# MAIN-BOARD.net
KiCad netlist of a schematic drawn in Altium Designer
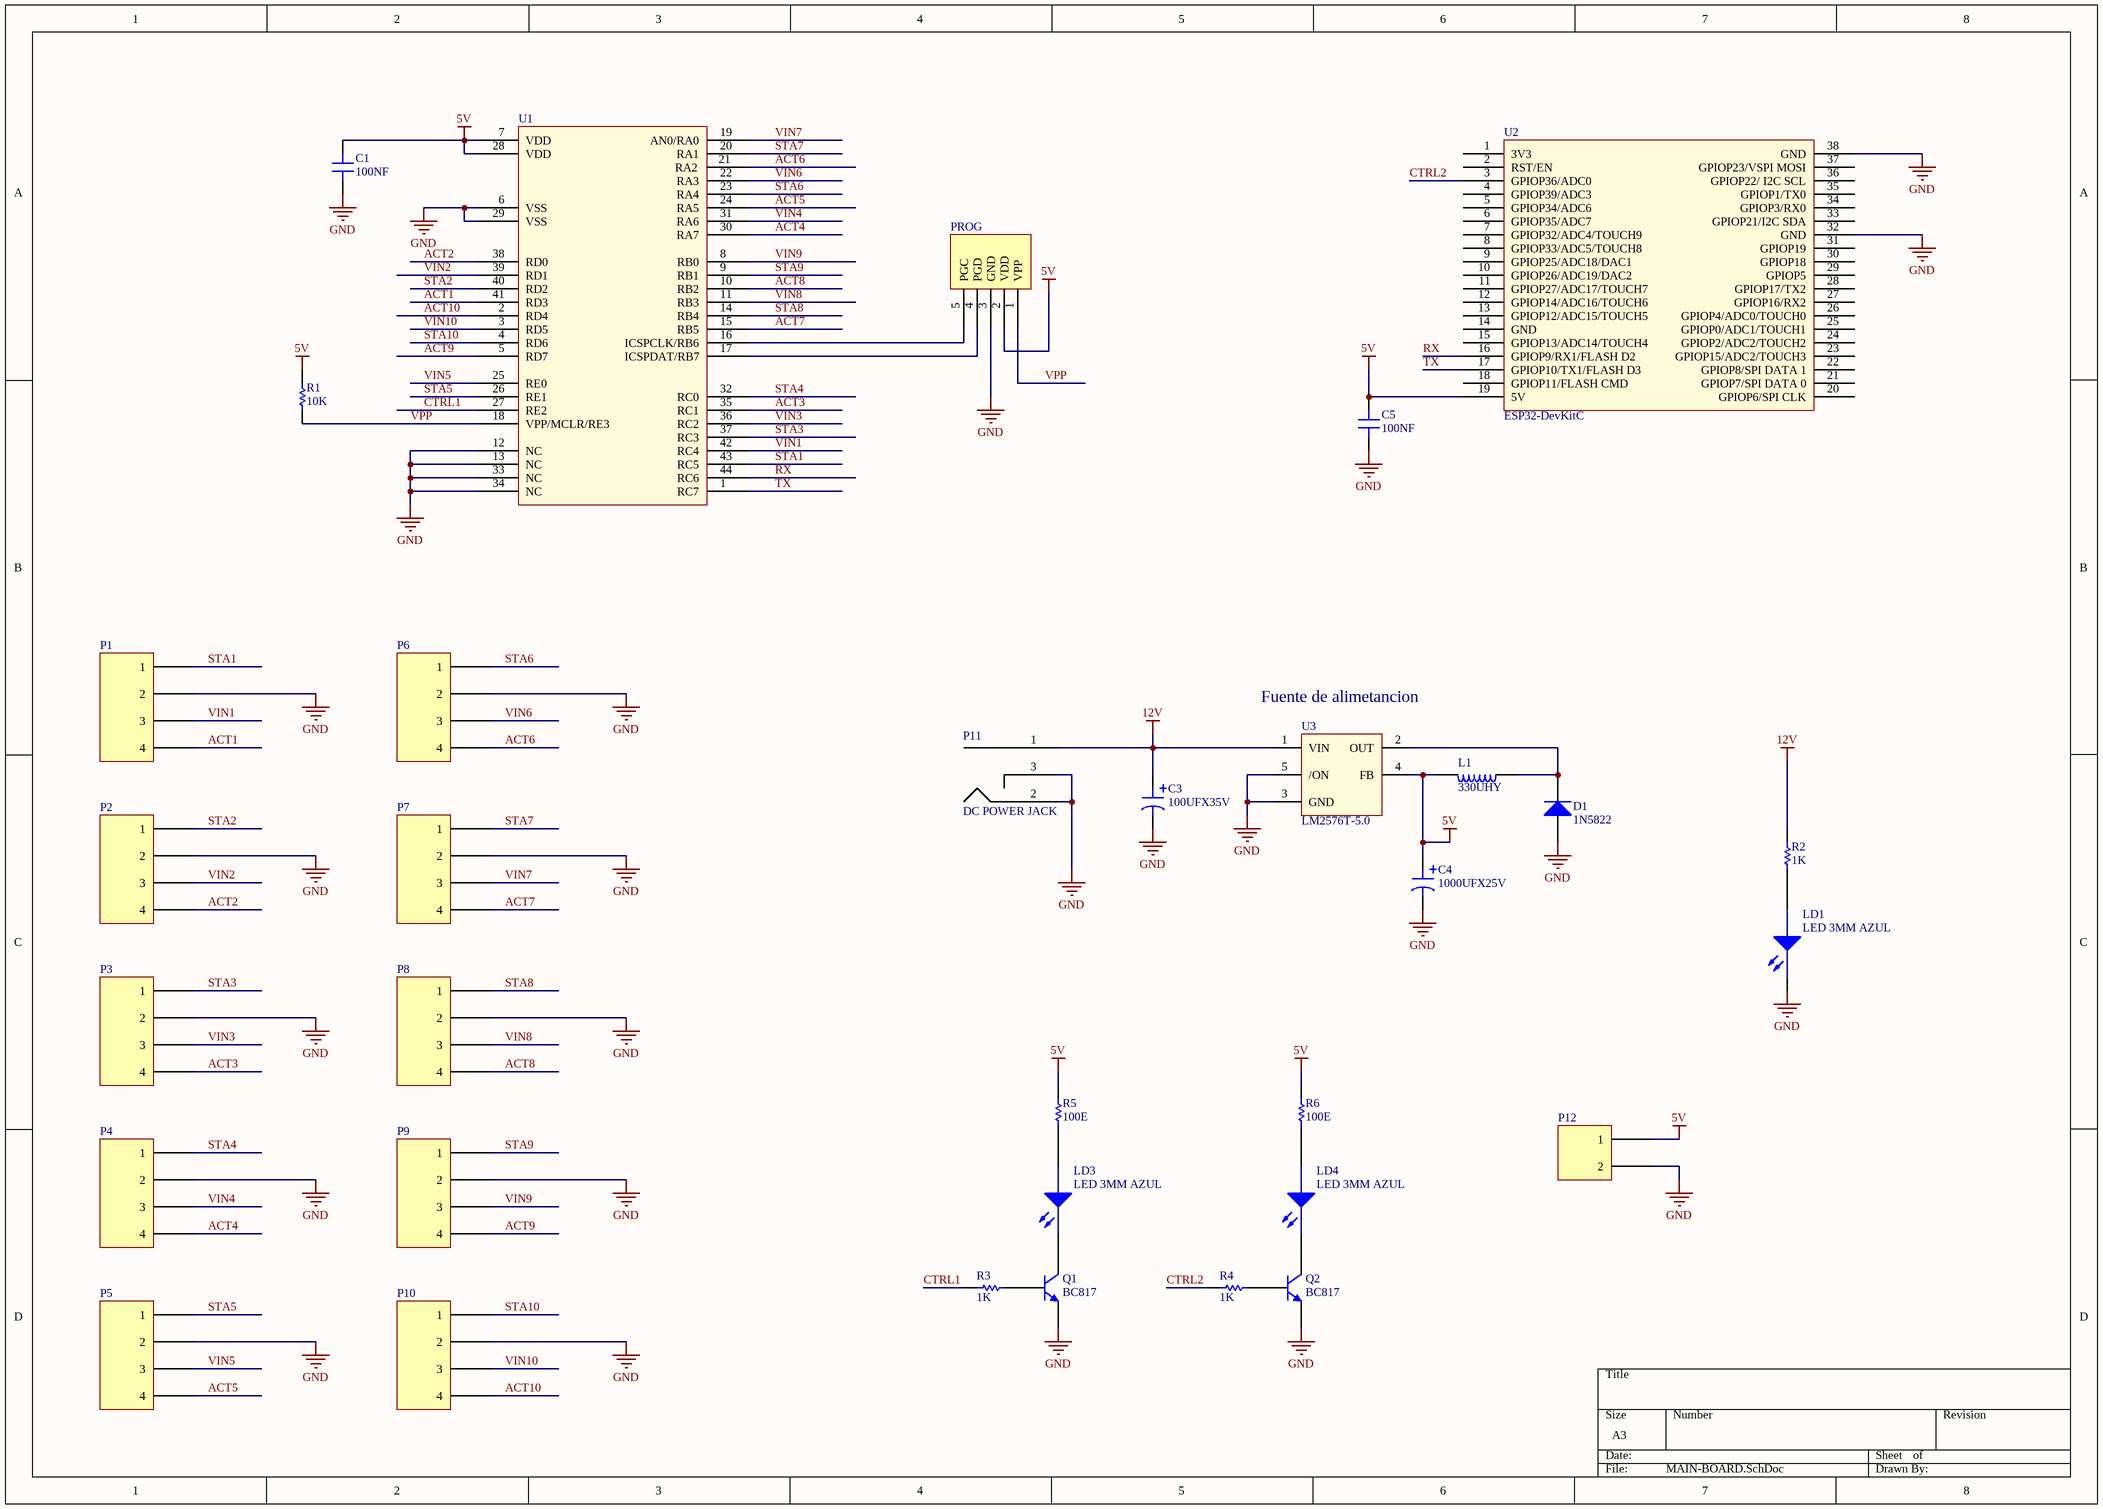
[diagram p0: MAIN-BOARD.SchDoc]

(export (version "E")
  (design (tool "Eeschema 10.0.6"))
  (components
    (comp (ref "C1")
      (value "100NF")
      (footprint "CAP.SMD.0805")
      (description "100NFX50V X7R 10% CER.MULT. SMD 0805")
      (libsource (lib "Libreria-Capacitores") (part "Capacitor 100NFX50V X7R 10% CER.MULT. SMD 0805"))
    )
    (comp (ref "C3")
      (value "100UFX35V")
      (footprint "CAP-ELEC-8X11")
      (description "100UFX35V 85°C 8x11 ELE.RAD AISHI")
      (libsource (lib "Libreria-Capacitores") (part "Capacitor Electrolitico 100UFX35V 85°C 8x11 ELE.RAD AISHI"))
    )
    (comp (ref "C4")
      (value "1000UFX25V")
      (footprint "CAP-ELEC-12.5X20")
      (description "1000UFX25V 85°C 12.5X20 ELE.RAD AISHI")
      (libsource (lib "Libreria-Capacitores") (part "Capacitor Electrolitico 1000UFX25V 85°C 12.5X20 ELE.RAD AISHI"))
    )
    (comp (ref "C5")
      (value "100NF")
      (footprint "CAP.SMD.0805")
      (description "100NFX50V X7R 10% CER.MULT. SMD 0805")
      (libsource (lib "Libreria-Capacitores") (part "Capacitor 100NFX50V X7R 10% CER.MULT. SMD 0805"))
    )
    (comp (ref "D1")
      (value "1N5822")
      (footprint "Diode 1N5822")
      (description "Diodo Schottky 1N5822 3A 40V")
      (libsource (lib "Libreria-Diodos") (part "Diodo Schottky 1N5822 3A 40V"))
    )
    (comp (ref "L1")
      (value "330UHY")
      (footprint "Inductor Radial DR1213")
      (description "330UHY 0.3R 1.4A RAD. 15.5X15.5MM")
      (libsource (lib "Libreria-Inductores") (part "Inductor Radial 330UHY 0.3R 1.4A RAD. 15.5X15.5MM"))
    )
    (comp (ref "LD1")
      (value "LED 3MM AZUL")
      (footprint "LED 3MM AZUL")
      (description "LED 3MM AZUL WC SUPER BRILLO 1250mcd 30潞 204-10SUBC/C470/S400-A6 PATAS 14MM")
      (libsource (lib "Libreria-LEDs") (part "LED 3MM AZUL WC SUPER BRILLO 1250mcd 30潞 204-10SUBC/C470/S400-A6 PATAS 14MM"))
    )
    (comp (ref "LD3")
      (value "LED 3MM AZUL")
      (footprint "LED 3MM AZUL")
      (description "LED 3MM AZUL WC SUPER BRILLO 1250mcd 30潞 204-10SUBC/C470/S400-A6 PATAS 14MM")
      (libsource (lib "Libreria-LEDs") (part "LED 3MM AZUL WC SUPER BRILLO 1250mcd 30潞 204-10SUBC/C470/S400-A6 PATAS 14MM"))
    )
    (comp (ref "LD4")
      (value "LED 3MM AZUL")
      (footprint "LED 3MM AZUL")
      (description "LED 3MM AZUL WC SUPER BRILLO 1250mcd 30潞 204-10SUBC/C470/S400-A6 PATAS 14MM")
      (libsource (lib "Libreria-LEDs") (part "LED 3MM AZUL WC SUPER BRILLO 1250mcd 30潞 204-10SUBC/C470/S400-A6 PATAS 14MM"))
    )
    (comp (ref "P1")
      (value "CONECTOR PWXXS MA-04 VERTICAL P=3.96MM PW0")
      (footprint "CONECTOR PWXXS MA-04 VERTICAL P=3.96MM")
      (libsource (lib "Libreria-Conectores") (part "CONECTOR PWXXS MA-04 VERTICAL P=3.96MM PW04S"))
    )
    (comp (ref "P2")
      (value "CONECTOR PWXXS MA-04 VERTICAL P=3.96MM PW0")
      (footprint "CONECTOR PWXXS MA-04 VERTICAL P=3.96MM")
      (libsource (lib "Libreria-Conectores") (part "CONECTOR PWXXS MA-04 VERTICAL P=3.96MM PW04S"))
    )
    (comp (ref "P3")
      (value "CONECTOR PWXXS MA-04 VERTICAL P=3.96MM PW0")
      (footprint "CONECTOR PWXXS MA-04 VERTICAL P=3.96MM")
      (libsource (lib "Libreria-Conectores") (part "CONECTOR PWXXS MA-04 VERTICAL P=3.96MM PW04S"))
    )
    (comp (ref "P4")
      (value "CONECTOR PWXXS MA-04 VERTICAL P=3.96MM PW0")
      (footprint "CONECTOR PWXXS MA-04 VERTICAL P=3.96MM")
      (libsource (lib "Libreria-Conectores") (part "CONECTOR PWXXS MA-04 VERTICAL P=3.96MM PW04S"))
    )
    (comp (ref "P5")
      (value "CONECTOR PWXXS MA-04 VERTICAL P=3.96MM PW0")
      (footprint "CONECTOR PWXXS MA-04 VERTICAL P=3.96MM")
      (libsource (lib "Libreria-Conectores") (part "CONECTOR PWXXS MA-04 VERTICAL P=3.96MM PW04S"))
    )
    (comp (ref "P6")
      (value "CONECTOR PWXXS MA-04 VERTICAL P=3.96MM PW0")
      (footprint "CONECTOR PWXXS MA-04 VERTICAL P=3.96MM")
      (libsource (lib "Libreria-Conectores") (part "CONECTOR PWXXS MA-04 VERTICAL P=3.96MM PW04S"))
    )
    (comp (ref "P7")
      (value "CONECTOR PWXXS MA-04 VERTICAL P=3.96MM PW0")
      (footprint "CONECTOR PWXXS MA-04 VERTICAL P=3.96MM")
      (libsource (lib "Libreria-Conectores") (part "CONECTOR PWXXS MA-04 VERTICAL P=3.96MM PW04S"))
    )
    (comp (ref "P8")
      (value "CONECTOR PWXXS MA-04 VERTICAL P=3.96MM PW0")
      (footprint "CONECTOR PWXXS MA-04 VERTICAL P=3.96MM")
      (libsource (lib "Libreria-Conectores") (part "CONECTOR PWXXS MA-04 VERTICAL P=3.96MM PW04S"))
    )
    (comp (ref "P9")
      (value "CONECTOR PWXXS MA-04 VERTICAL P=3.96MM PW0")
      (footprint "CONECTOR PWXXS MA-04 VERTICAL P=3.96MM")
      (libsource (lib "Libreria-Conectores") (part "CONECTOR PWXXS MA-04 VERTICAL P=3.96MM PW04S"))
    )
    (comp (ref "P10")
      (value "CONECTOR PWXXS MA-04 VERTICAL P=3.96MM PW0")
      (footprint "CONECTOR PWXXS MA-04 VERTICAL P=3.96MM")
      (libsource (lib "Libreria-Conectores") (part "CONECTOR PWXXS MA-04 VERTICAL P=3.96MM PW04S"))
    )
    (comp (ref "P11")
      (value "DC POWER JACK")
      (footprint "VAR-DC-JACK")
      (description "DC POWER JACK 90 GRA. 2MM")
      (libsource (lib "Libreria-Varios") (part "DC POWER JACK 90 GRA. 2MM"))
    )
    (comp (ref "P12")
      (value "BORNE 2P P=5MM 1.5MM2 15A AZUL XY301V-2P")
      (footprint "CON-BOR-X2-5MM")
      (libsource (lib "Libreria-Conectores") (part "BORNE 2P P=5MM 1.5MM2 15A AZUL XY301V-2P"))
    )
    (comp (ref "PROG")
      (value "In-Serial Circuit Programmer Header")
      (footprint "PIC ICSP")
      (libsource (lib "Libreria-Conectores") (part "In-Serial Circuit Programmer Header"))
    )
    (comp (ref "Q1")
      (value "BC817")
      (footprint "NPN.SMD.SOT23")
      (description "BC817-40 TRA.NPN 45V0.5A 0.25W SOT23")
      (libsource (lib "Libreria-Transistores") (part "Transistor BC817-40 TRA.NPN 45V0.5A 0.25W SOT23"))
    )
    (comp (ref "Q2")
      (value "BC817")
      (footprint "NPN.SMD.SOT23")
      (description "BC817-40 TRA.NPN 45V0.5A 0.25W SOT23")
      (libsource (lib "Libreria-Transistores") (part "Transistor BC817-40 TRA.NPN 45V0.5A 0.25W SOT23"))
    )
    (comp (ref "R1")
      (value "10K")
      (footprint "RES.SMD.103")
      (description "10K 5% 0805 1/8W RES.SMD")
      (libsource (lib "Libreria-Resistencias") (part "Resistencia 10K 5% 0805 1/8W"))
    )
    (comp (ref "R2")
      (value "1K")
      (footprint "RES.SMD.102")
      (description "1K 5% 0805 1/8W RES.SMD")
      (libsource (lib "Libreria-Resistencias") (part "Resistencia 1K 5% 0805 1/8W"))
    )
    (comp (ref "R3")
      (value "1K")
      (footprint "RES.SMD.102")
      (description "1K 5% 0805 1/8W RES.SMD")
      (libsource (lib "Libreria-Resistencias") (part "Resistencia 1K 5% 0805 1/8W"))
    )
    (comp (ref "R4")
      (value "1K")
      (footprint "RES.SMD.102")
      (description "1K 5% 0805 1/8W RES.SMD")
      (libsource (lib "Libreria-Resistencias") (part "Resistencia 1K 5% 0805 1/8W"))
    )
    (comp (ref "R5")
      (value "100E")
      (footprint "RES.SMD.101")
      (description "100E 5% 0805 1/8W RES.SMD")
      (libsource (lib "Libreria-Resistencias") (part "Resistencia 100E 5% 0805 1/8W"))
    )
    (comp (ref "R6")
      (value "100E")
      (footprint "RES.SMD.101")
      (description "100E 5% 0805 1/8W RES.SMD")
      (libsource (lib "Libreria-Resistencias") (part "Resistencia 100E 5% 0805 1/8W"))
    )
    (comp (ref "U1")
      (value "PIC16F18875-I/PT 44 TQFP 14KB Flash, 1KB RAM, 256B EE, 10b ADC2")
      (footprint "44TQFP - PIC16F18875")
      (libsource (lib "Libreria-Semiconductores") (part "PIC16F18875-I/PT 44 TQFP 14KB Flash, 1KB RAM, 256B EE, 10b ADC2"))
    )
    (comp (ref "U2")
      (value "ESP32-DevKitC")
      (footprint "ESP32-DevKitC")
      (libsource (lib "Libreria-Arduino") (part "ESP32-DevKitC"))
    )
    (comp (ref "U3")
      (value "LM2576T-5.0")
      (footprint "LM2576T-5.0")
      (description "LM2576T-5.0 TO220 3A.STEP.DOWN.VOLT.REG.")
      (libsource (lib "Libreria-Semiconductores") (part "LM2576T-5.0 TO220 3A.STEP.DOWN.VOLT.REG."))
    )
  )
  (nets
    (net (code "1") (name "/ACT1") (class "Default")
      (node (ref "P1") (pin "4") (pinfunction "4_4") (pintype "passive"))
      (node (ref "U1") (pin "41") (pinfunction "RD3_41") (pintype "passive"))
    )
    (net (code "2") (name "/ACT2") (class "Default")
      (node (ref "P2") (pin "4") (pinfunction "4_4") (pintype "passive"))
      (node (ref "U1") (pin "38") (pinfunction "RD0_38") (pintype "passive"))
    )
    (net (code "3") (name "/ACT3") (class "Default")
      (node (ref "P3") (pin "4") (pinfunction "4_4") (pintype "passive"))
      (node (ref "U1") (pin "35") (pinfunction "RC1_35") (pintype "passive"))
    )
    (net (code "4") (name "/ACT4") (class "Default")
      (node (ref "P4") (pin "4") (pinfunction "4_4") (pintype "passive"))
      (node (ref "U1") (pin "30") (pinfunction "RA7_30") (pintype "passive"))
    )
    (net (code "5") (name "/ACT5") (class "Default")
      (node (ref "P5") (pin "4") (pinfunction "4_4") (pintype "passive"))
      (node (ref "U1") (pin "24") (pinfunction "RA5_24") (pintype "passive"))
    )
    (net (code "6") (name "/ACT6") (class "Default")
      (node (ref "P6") (pin "4") (pinfunction "4_4") (pintype "passive"))
      (node (ref "U1") (pin "21") (pinfunction "RA2_21") (pintype "passive"))
    )
    (net (code "7") (name "/ACT7") (class "Default")
      (node (ref "P7") (pin "4") (pinfunction "4_4") (pintype "passive"))
      (node (ref "U1") (pin "15") (pinfunction "RB5_15") (pintype "passive"))
    )
    (net (code "8") (name "/ACT8") (class "Default")
      (node (ref "P8") (pin "4") (pinfunction "4_4") (pintype "passive"))
      (node (ref "U1") (pin "10") (pinfunction "RB2_10") (pintype "passive"))
    )
    (net (code "9") (name "/ACT9") (class "Default")
      (node (ref "P9") (pin "4") (pinfunction "4_4") (pintype "passive"))
      (node (ref "U1") (pin "5") (pinfunction "RD7_5") (pintype "passive"))
    )
    (net (code "10") (name "/ACT10") (class "Default")
      (node (ref "P10") (pin "4") (pinfunction "4_4") (pintype "passive"))
      (node (ref "U1") (pin "2") (pinfunction "RD4_2") (pintype "passive"))
    )
    (net (code "11") (name "/CTRL1") (class "Default")
      (node (ref "R3") (pin "2") (pinfunction "2_2") (pintype "passive"))
      (node (ref "U1") (pin "27") (pinfunction "RE2_27") (pintype "passive"))
    )
    (net (code "12") (name "/CTRL2") (class "Default")
      (node (ref "R4") (pin "2") (pinfunction "2_2") (pintype "passive"))
      (node (ref "U2") (pin "3") (pinfunction "GPIOP36/ADC0_3") (pintype "passive"))
    )
    (net (code "13") (name "/RX") (class "Default")
      (node (ref "U1") (pin "44") (pinfunction "RC6_44") (pintype "passive"))
      (node (ref "U2") (pin "16") (pinfunction "GPIOP9/RX1/FLASH_D2_16") (pintype "passive"))
    )
    (net (code "14") (name "/STA1") (class "Default")
      (node (ref "P1") (pin "1") (pinfunction "1_1") (pintype "passive"))
      (node (ref "U1") (pin "43") (pinfunction "RC5_43") (pintype "passive"))
    )
    (net (code "15") (name "/STA2") (class "Default")
      (node (ref "P2") (pin "1") (pinfunction "1_1") (pintype "passive"))
      (node (ref "U1") (pin "40") (pinfunction "RD2_40") (pintype "passive"))
    )
    (net (code "16") (name "/STA3") (class "Default")
      (node (ref "P3") (pin "1") (pinfunction "1_1") (pintype "passive"))
      (node (ref "U1") (pin "37") (pinfunction "RC3_37") (pintype "passive"))
    )
    (net (code "17") (name "/STA4") (class "Default")
      (node (ref "P4") (pin "1") (pinfunction "1_1") (pintype "passive"))
      (node (ref "U1") (pin "32") (pinfunction "RC0_32") (pintype "passive"))
    )
    (net (code "18") (name "/STA5") (class "Default")
      (node (ref "P5") (pin "1") (pinfunction "1_1") (pintype "passive"))
      (node (ref "U1") (pin "26") (pinfunction "RE1_26") (pintype "passive"))
    )
    (net (code "19") (name "/STA6") (class "Default")
      (node (ref "P6") (pin "1") (pinfunction "1_1") (pintype "passive"))
      (node (ref "U1") (pin "23") (pinfunction "RA4_23") (pintype "passive"))
    )
    (net (code "20") (name "/STA7") (class "Default")
      (node (ref "P7") (pin "1") (pinfunction "1_1") (pintype "passive"))
      (node (ref "U1") (pin "20") (pinfunction "RA1_20") (pintype "passive"))
    )
    (net (code "21") (name "/STA8") (class "Default")
      (node (ref "P8") (pin "1") (pinfunction "1_1") (pintype "passive"))
      (node (ref "U1") (pin "14") (pinfunction "RB4_14") (pintype "passive"))
    )
    (net (code "22") (name "/STA9") (class "Default")
      (node (ref "P9") (pin "1") (pinfunction "1_1") (pintype "passive"))
      (node (ref "U1") (pin "9") (pinfunction "RB1_9") (pintype "passive"))
    )
    (net (code "23") (name "/STA10") (class "Default")
      (node (ref "P10") (pin "1") (pinfunction "1_1") (pintype "passive"))
      (node (ref "U1") (pin "4") (pinfunction "RD6_4") (pintype "passive"))
    )
    (net (code "24") (name "/TX") (class "Default")
      (node (ref "U1") (pin "1") (pinfunction "RC7_1") (pintype "passive"))
      (node (ref "U2") (pin "17") (pinfunction "GPIOP10/TX1/FLASH_D3_17") (pintype "passive"))
    )
    (net (code "25") (name "/VIN1") (class "Default")
      (node (ref "P1") (pin "3") (pinfunction "3_3") (pintype "passive"))
      (node (ref "U1") (pin "42") (pinfunction "RC4_42") (pintype "passive"))
    )
    (net (code "26") (name "/VIN2") (class "Default")
      (node (ref "P2") (pin "3") (pinfunction "3_3") (pintype "passive"))
      (node (ref "U1") (pin "39") (pinfunction "RD1_39") (pintype "passive"))
    )
    (net (code "27") (name "/VIN3") (class "Default")
      (node (ref "P3") (pin "3") (pinfunction "3_3") (pintype "passive"))
      (node (ref "U1") (pin "36") (pinfunction "RC2_36") (pintype "passive"))
    )
    (net (code "28") (name "/VIN4") (class "Default")
      (node (ref "P4") (pin "3") (pinfunction "3_3") (pintype "passive"))
      (node (ref "U1") (pin "31") (pinfunction "RA6_31") (pintype "passive"))
    )
    (net (code "29") (name "/VIN5") (class "Default")
      (node (ref "P5") (pin "3") (pinfunction "3_3") (pintype "passive"))
      (node (ref "U1") (pin "25") (pinfunction "RE0_25") (pintype "passive"))
    )
    (net (code "30") (name "/VIN6") (class "Default")
      (node (ref "P6") (pin "3") (pinfunction "3_3") (pintype "passive"))
      (node (ref "U1") (pin "22") (pinfunction "RA3_22") (pintype "passive"))
    )
    (net (code "31") (name "/VIN7") (class "Default")
      (node (ref "P7") (pin "3") (pinfunction "3_3") (pintype "passive"))
      (node (ref "U1") (pin "19") (pinfunction "AN0/RA0_19") (pintype "passive"))
    )
    (net (code "32") (name "/VIN8") (class "Default")
      (node (ref "P8") (pin "3") (pinfunction "3_3") (pintype "passive"))
      (node (ref "U1") (pin "11") (pinfunction "RB3_11") (pintype "passive"))
    )
    (net (code "33") (name "/VIN9") (class "Default")
      (node (ref "P9") (pin "3") (pinfunction "3_3") (pintype "passive"))
      (node (ref "U1") (pin "8") (pinfunction "RB0_8") (pintype "passive"))
    )
    (net (code "34") (name "/VIN10") (class "Default")
      (node (ref "P10") (pin "3") (pinfunction "3_3") (pintype "passive"))
      (node (ref "U1") (pin "3") (pinfunction "RD5_3") (pintype "passive"))
    )
    (net (code "35") (name "/VPP") (class "Default")
      (node (ref "PROG") (pin "1") (pinfunction "VPP_1") (pintype "passive"))
      (node (ref "R1") (pin "1") (pinfunction "1_1") (pintype "passive"))
      (node (ref "U1") (pin "18") (pinfunction "VPP/MCLR/RE3_18") (pintype "passive"))
    )
    (net (code "36") (name "5V") (class "Default")
      (node (ref "C1") (pin "2") (pinfunction "2_2") (pintype "passive"))
      (node (ref "C4") (pin "1") (pinfunction "1_1") (pintype "passive"))
      (node (ref "C5") (pin "2") (pinfunction "2_2") (pintype "passive"))
      (node (ref "L1") (pin "1") (pinfunction "1_1") (pintype "passive"))
      (node (ref "P12") (pin "1") (pinfunction "1_1") (pintype "passive"))
      (node (ref "PROG") (pin "2") (pinfunction "VDD_2") (pintype "passive"))
      (node (ref "R1") (pin "2") (pinfunction "2_2") (pintype "passive"))
      (node (ref "R5") (pin "2") (pinfunction "2_2") (pintype "passive"))
      (node (ref "R6") (pin "2") (pinfunction "2_2") (pintype "passive"))
      (node (ref "U1") (pin "28") (pinfunction "VDD_28") (pintype "passive"))
      (node (ref "U1") (pin "7") (pinfunction "VDD_7") (pintype "passive"))
      (node (ref "U2") (pin "19") (pinfunction "5V_19") (pintype "passive"))
      (node (ref "U3") (pin "4") (pinfunction "FB_4") (pintype "passive"))
    )
    (net (code "37") (name "12V") (class "Default")
      (node (ref "C3") (pin "1") (pinfunction "1_1") (pintype "passive"))
      (node (ref "P11") (pin "1") (pinfunction "1_1") (pintype "passive"))
      (node (ref "R2") (pin "2") (pinfunction "2_2") (pintype "passive"))
      (node (ref "U3") (pin "1") (pinfunction "VIN_1") (pintype "passive"))
    )
    (net (code "38") (name "GND") (class "Default")
      (node (ref "C1") (pin "1") (pinfunction "1_1") (pintype "passive"))
      (node (ref "C3") (pin "2") (pinfunction "2_2") (pintype "passive"))
      (node (ref "C4") (pin "2") (pinfunction "2_2") (pintype "passive"))
      (node (ref "C5") (pin "1") (pinfunction "1_1") (pintype "passive"))
      (node (ref "D1") (pin "A") (pinfunction "A_A") (pintype "passive"))
      (node (ref "LD1") (pin "K") (pinfunction "KB_K") (pintype "passive"))
      (node (ref "P1") (pin "2") (pinfunction "2_2") (pintype "passive"))
      (node (ref "P10") (pin "2") (pinfunction "2_2") (pintype "passive"))
      (node (ref "P11") (pin "2") (pinfunction "2_2") (pintype "passive"))
      (node (ref "P11") (pin "3") (pinfunction "3_3") (pintype "passive"))
      (node (ref "P12") (pin "2") (pinfunction "2_2") (pintype "passive"))
      (node (ref "P2") (pin "2") (pinfunction "2_2") (pintype "passive"))
      (node (ref "P3") (pin "2") (pinfunction "2_2") (pintype "passive"))
      (node (ref "P4") (pin "2") (pinfunction "2_2") (pintype "passive"))
      (node (ref "P5") (pin "2") (pinfunction "2_2") (pintype "passive"))
      (node (ref "P6") (pin "2") (pinfunction "2_2") (pintype "passive"))
      (node (ref "P7") (pin "2") (pinfunction "2_2") (pintype "passive"))
      (node (ref "P8") (pin "2") (pinfunction "2_2") (pintype "passive"))
      (node (ref "P9") (pin "2") (pinfunction "2_2") (pintype "passive"))
      (node (ref "PROG") (pin "3") (pinfunction "GND_3") (pintype "passive"))
      (node (ref "Q1") (pin "2") (pinfunction "E_2") (pintype "passive"))
      (node (ref "Q2") (pin "2") (pinfunction "E_2") (pintype "passive"))
      (node (ref "U1") (pin "12") (pinfunction "NC_12") (pintype "passive"))
      (node (ref "U1") (pin "13") (pinfunction "NC_13") (pintype "passive"))
      (node (ref "U1") (pin "29") (pinfunction "VSS_29") (pintype "passive"))
      (node (ref "U1") (pin "33") (pinfunction "NC_33") (pintype "passive"))
      (node (ref "U1") (pin "34") (pinfunction "NC_34") (pintype "passive"))
      (node (ref "U1") (pin "6") (pinfunction "VSS_6") (pintype "passive"))
      (node (ref "U2") (pin "32") (pinfunction "GND_32") (pintype "passive"))
      (node (ref "U2") (pin "38") (pinfunction "GND_38") (pintype "passive"))
      (node (ref "U3") (pin "3") (pinfunction "GND_3") (pintype "passive"))
      (node (ref "U3") (pin "5") (pinfunction "/ON_5") (pintype "passive"))
    )
    (net (code "39") (name "Net-(LD1-AB)") (class "Default")
      (node (ref "LD1") (pin "A") (pinfunction "AB_A") (pintype "passive"))
      (node (ref "R2") (pin "1") (pinfunction "1_1") (pintype "passive"))
    )
    (net (code "40") (name "Net-(LD3-AB)") (class "Default")
      (node (ref "LD3") (pin "A") (pinfunction "AB_A") (pintype "passive"))
      (node (ref "R5") (pin "1") (pinfunction "1_1") (pintype "passive"))
    )
    (net (code "41") (name "Net-(LD3-KB)") (class "Default")
      (node (ref "LD3") (pin "K") (pinfunction "KB_K") (pintype "passive"))
      (node (ref "Q1") (pin "3") (pinfunction "C_3") (pintype "passive"))
    )
    (net (code "42") (name "Net-(LD4-AB)") (class "Default")
      (node (ref "LD4") (pin "A") (pinfunction "AB_A") (pintype "passive"))
      (node (ref "R6") (pin "1") (pinfunction "1_1") (pintype "passive"))
    )
    (net (code "43") (name "Net-(LD4-KB)") (class "Default")
      (node (ref "LD4") (pin "K") (pinfunction "KB_K") (pintype "passive"))
      (node (ref "Q2") (pin "3") (pinfunction "C_3") (pintype "passive"))
    )
    (net (code "44") (name "Net-(PROG-PGC)") (class "Default")
      (node (ref "PROG") (pin "5") (pinfunction "PGC_5") (pintype "passive"))
      (node (ref "U1") (pin "16") (pinfunction "ICSPCLK/RB6_16") (pintype "passive"))
    )
    (net (code "45") (name "Net-(PROG-PGD)") (class "Default")
      (node (ref "PROG") (pin "4") (pinfunction "PGD_4") (pintype "passive"))
      (node (ref "U1") (pin "17") (pinfunction "ICSPDAT/RB7_17") (pintype "passive"))
    )
    (net (code "46") (name "Net-(Q1-B)") (class "Default")
      (node (ref "Q1") (pin "1") (pinfunction "B_1") (pintype "passive"))
      (node (ref "R3") (pin "1") (pinfunction "1_1") (pintype "passive"))
    )
    (net (code "47") (name "Net-(Q2-B)") (class "Default")
      (node (ref "Q2") (pin "1") (pinfunction "B_1") (pintype "passive"))
      (node (ref "R4") (pin "1") (pinfunction "1_1") (pintype "passive"))
    )
    (net (code "48") (name "Net-(U3-OUT)") (class "Default")
      (node (ref "D1") (pin "K") (pinfunction "K_K") (pintype "passive"))
      (node (ref "L1") (pin "2") (pinfunction "2_2") (pintype "passive"))
      (node (ref "U3") (pin "2") (pinfunction "OUT_2") (pintype "passive"))
    )
    (net (code "49") (name "unconnected-(U2-3V3-Pad1)") (class "Default")
      (node (ref "U2") (pin "1") (pinfunction "3V3_1") (pintype "passive"))
    )
    (net (code "50") (name "unconnected-(U2-GND-Pad14)") (class "Default")
      (node (ref "U2") (pin "14") (pinfunction "GND_14") (pintype "passive"))
    )
    (net (code "51") (name "unconnected-(U2-GPIOP0{slash}ADC1{slash}TOUCH1-Pad25)") (class "Default")
      (node (ref "U2") (pin "25") (pinfunction "GPIOP0/ADC1/TOUCH1_25") (pintype "passive"))
    )
    (net (code "52") (name "unconnected-(U2-GPIOP1{slash}TX0-Pad35)") (class "Default")
      (node (ref "U2") (pin "35") (pinfunction "GPIOP1/TX0_35") (pintype "passive"))
    )
    (net (code "53") (name "unconnected-(U2-GPIOP2{slash}ADC2{slash}TOUCH2-Pad24)") (class "Default")
      (node (ref "U2") (pin "24") (pinfunction "GPIOP2/ADC2/TOUCH2_24") (pintype "passive"))
    )
    (net (code "54") (name "unconnected-(U2-GPIOP3{slash}RX0-Pad34)") (class "Default")
      (node (ref "U2") (pin "34") (pinfunction "GPIOP3/RX0_34") (pintype "passive"))
    )
    (net (code "55") (name "unconnected-(U2-GPIOP4{slash}ADC0{slash}TOUCH0-Pad26)") (class "Default")
      (node (ref "U2") (pin "26") (pinfunction "GPIOP4/ADC0/TOUCH0_26") (pintype "passive"))
    )
    (net (code "56") (name "unconnected-(U2-GPIOP5-Pad29)") (class "Default")
      (node (ref "U2") (pin "29") (pinfunction "GPIOP5_29") (pintype "passive"))
    )
    (net (code "57") (name "unconnected-(U2-GPIOP6{slash}SPI_CLK-Pad20)") (class "Default")
      (node (ref "U2") (pin "20") (pinfunction "GPIOP6/SPI_CLK_20") (pintype "passive"))
    )
    (net (code "58") (name "unconnected-(U2-GPIOP7{slash}SPI_DATA_0-Pad21)") (class "Default")
      (node (ref "U2") (pin "21") (pinfunction "GPIOP7/SPI_DATA_0_21") (pintype "passive"))
    )
    (net (code "59") (name "unconnected-(U2-GPIOP8{slash}SPI_DATA_1-Pad22)") (class "Default")
      (node (ref "U2") (pin "22") (pinfunction "GPIOP8/SPI_DATA_1_22") (pintype "passive"))
    )
    (net (code "60") (name "unconnected-(U2-GPIOP11{slash}FLASH_CMD-Pad18)") (class "Default")
      (node (ref "U2") (pin "18") (pinfunction "GPIOP11/FLASH_CMD_18") (pintype "passive"))
    )
    (net (code "61") (name "unconnected-(U2-GPIOP12{slash}ADC15{slash}TOUCH5-Pad13)") (class "Default")
      (node (ref "U2") (pin "13") (pinfunction "GPIOP12/ADC15/TOUCH5_13") (pintype "passive"))
    )
    (net (code "62") (name "unconnected-(U2-GPIOP13{slash}ADC14{slash}TOUCH4-Pad15)") (class "Default")
      (node (ref "U2") (pin "15") (pinfunction "GPIOP13/ADC14/TOUCH4_15") (pintype "passive"))
    )
    (net (code "63") (name "unconnected-(U2-GPIOP14{slash}ADC16{slash}TOUCH6-Pad12)") (class "Default")
      (node (ref "U2") (pin "12") (pinfunction "GPIOP14/ADC16/TOUCH6_12") (pintype "passive"))
    )
    (net (code "64") (name "unconnected-(U2-GPIOP15{slash}ADC2{slash}TOUCH3-Pad23)") (class "Default")
      (node (ref "U2") (pin "23") (pinfunction "GPIOP15/ADC2/TOUCH3_23") (pintype "passive"))
    )
    (net (code "65") (name "unconnected-(U2-GPIOP16{slash}RX2-Pad27)") (class "Default")
      (node (ref "U2") (pin "27") (pinfunction "GPIOP16/RX2_27") (pintype "passive"))
    )
    (net (code "66") (name "unconnected-(U2-GPIOP17{slash}TX2-Pad28)") (class "Default")
      (node (ref "U2") (pin "28") (pinfunction "GPIOP17/TX2_28") (pintype "passive"))
    )
    (net (code "67") (name "unconnected-(U2-GPIOP18-Pad30)") (class "Default")
      (node (ref "U2") (pin "30") (pinfunction "GPIOP18_30") (pintype "passive"))
    )
    (net (code "68") (name "unconnected-(U2-GPIOP19-Pad31)") (class "Default")
      (node (ref "U2") (pin "31") (pinfunction "GPIOP19_31") (pintype "passive"))
    )
    (net (code "69") (name "unconnected-(U2-GPIOP21{slash}I2C_SDA-Pad33)") (class "Default")
      (node (ref "U2") (pin "33") (pinfunction "GPIOP21/I2C_SDA_33") (pintype "passive"))
    )
    (net (code "70") (name "unconnected-(U2-GPIOP22{slash}_I2C_SCL-Pad36)") (class "Default")
      (node (ref "U2") (pin "36") (pinfunction "GPIOP22/_I2C_SCL_36") (pintype "passive"))
    )
    (net (code "71") (name "unconnected-(U2-GPIOP23{slash}VSPI_MOSI-Pad37)") (class "Default")
      (node (ref "U2") (pin "37") (pinfunction "GPIOP23/VSPI_MOSI_37") (pintype "passive"))
    )
    (net (code "72") (name "unconnected-(U2-GPIOP25{slash}ADC18{slash}DAC1-Pad9)") (class "Default")
      (node (ref "U2") (pin "9") (pinfunction "GPIOP25/ADC18/DAC1_9") (pintype "passive"))
    )
    (net (code "73") (name "unconnected-(U2-GPIOP26{slash}ADC19{slash}DAC2-Pad10)") (class "Default")
      (node (ref "U2") (pin "10") (pinfunction "GPIOP26/ADC19/DAC2_10") (pintype "passive"))
    )
    (net (code "74") (name "unconnected-(U2-GPIOP27{slash}ADC17{slash}TOUCH7-Pad11)") (class "Default")
      (node (ref "U2") (pin "11") (pinfunction "GPIOP27/ADC17/TOUCH7_11") (pintype "passive"))
    )
    (net (code "75") (name "unconnected-(U2-GPIOP32{slash}ADC4{slash}TOUCH9-Pad7)") (class "Default")
      (node (ref "U2") (pin "7") (pinfunction "GPIOP32/ADC4/TOUCH9_7") (pintype "passive"))
    )
    (net (code "76") (name "unconnected-(U2-GPIOP33{slash}ADC5{slash}TOUCH8-Pad8)") (class "Default")
      (node (ref "U2") (pin "8") (pinfunction "GPIOP33/ADC5/TOUCH8_8") (pintype "passive"))
    )
    (net (code "77") (name "unconnected-(U2-GPIOP34{slash}ADC6-Pad5)") (class "Default")
      (node (ref "U2") (pin "5") (pinfunction "GPIOP34/ADC6_5") (pintype "passive"))
    )
    (net (code "78") (name "unconnected-(U2-GPIOP35{slash}ADC7-Pad6)") (class "Default")
      (node (ref "U2") (pin "6") (pinfunction "GPIOP35/ADC7_6") (pintype "passive"))
    )
    (net (code "79") (name "unconnected-(U2-GPIOP39{slash}ADC3-Pad4)") (class "Default")
      (node (ref "U2") (pin "4") (pinfunction "GPIOP39/ADC3_4") (pintype "passive"))
    )
    (net (code "80") (name "unconnected-(U2-RST{slash}EN-Pad2)") (class "Default")
      (node (ref "U2") (pin "2") (pinfunction "RST/EN_2") (pintype "passive"))
    )
  )
)
